# MOSFET_Driver_Sheet4.net
KiCad netlist of a schematic drawn in Altium Designer
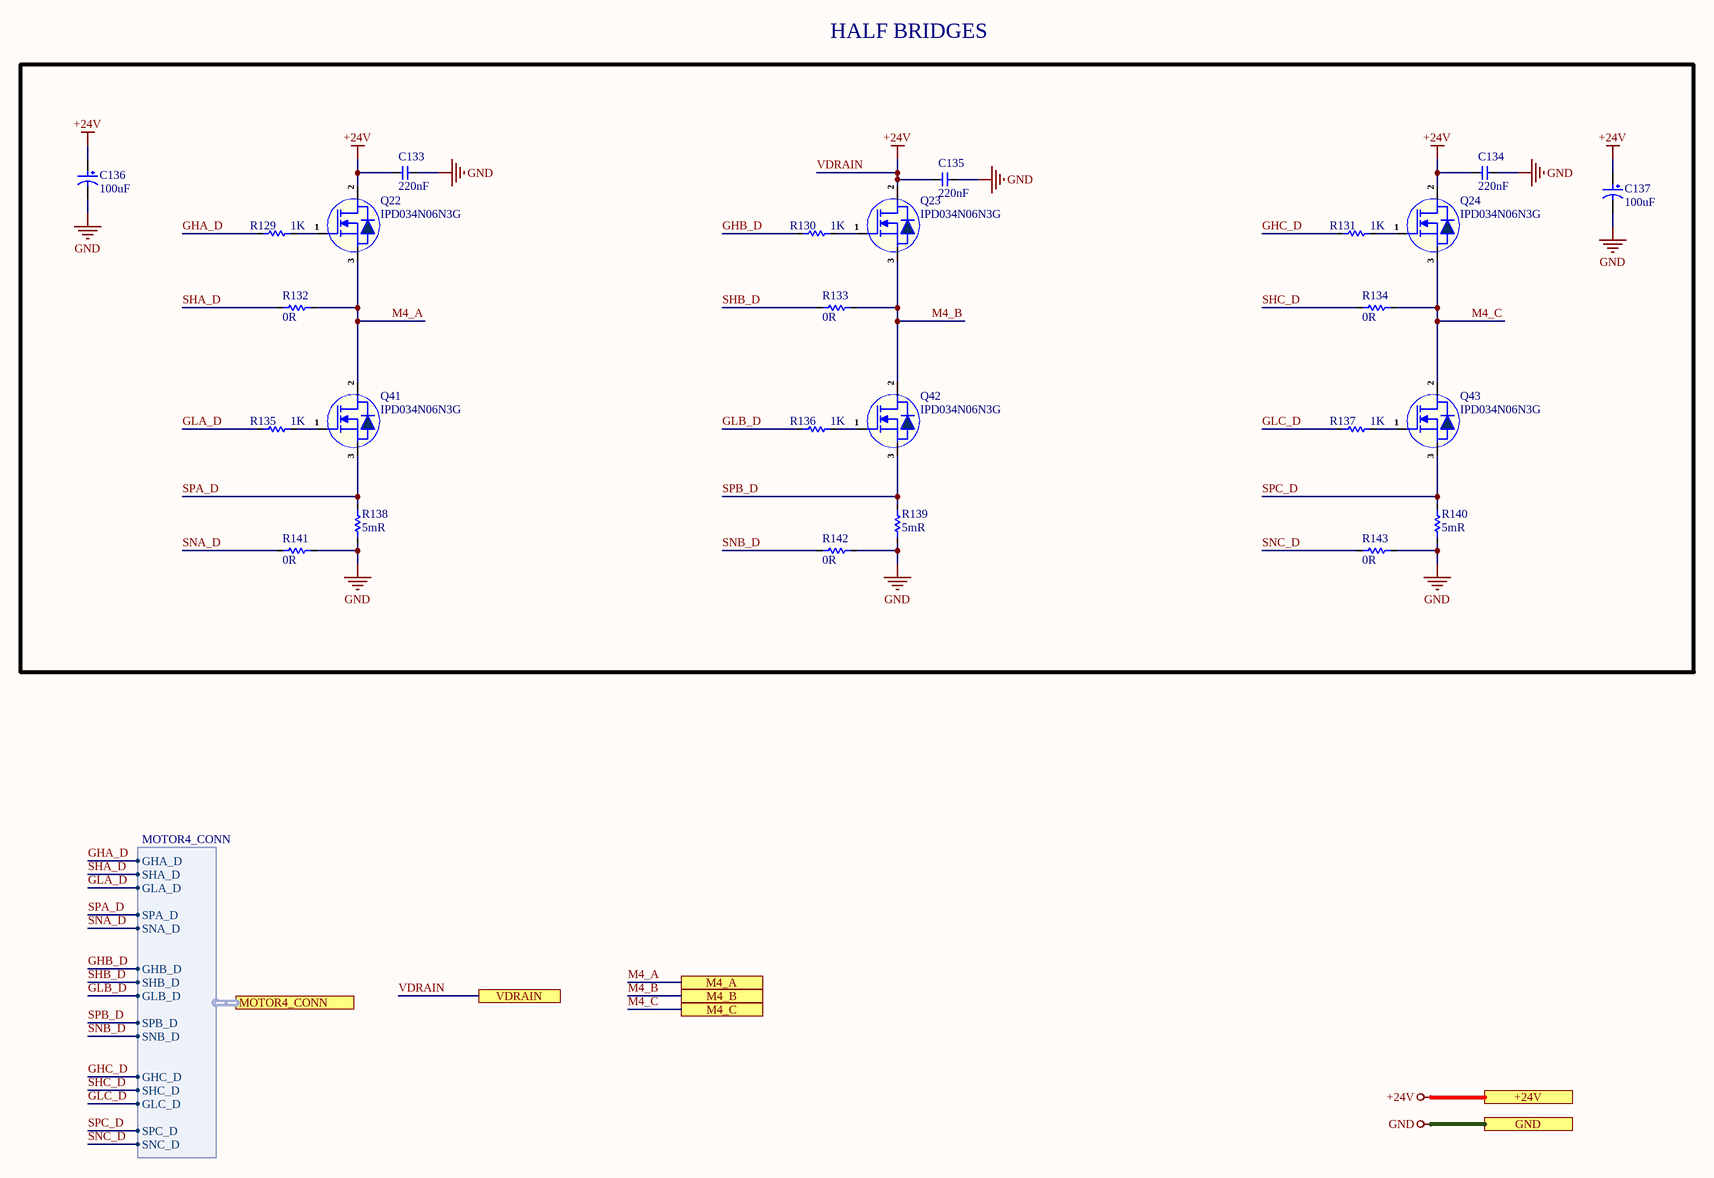
[diagram p0: MOSFET_Driver_Sheet4.SchDoc]

(export (version "E")
  (design (tool "Eeschema 10.0.6"))
  (components
    (comp (ref "C133")
      (value "220nF")
      (footprint "Cap-0805")
      (description "CAP CER 0.22UF 100V X7R 0805")
      (fields
        (field (name "MANUFACTURER") "Kyocera AVX")
        (field (name "MANUFACTURER PART NUMBER") "08051C224K4T2A")
      )
      (libsource (lib "eSpark Libraries") (part "08051C224K4T2A"))
    )
    (comp (ref "C134")
      (value "220nF")
      (footprint "Cap-0805")
      (description "CAP CER 0.22UF 100V X7R 0805")
      (fields
        (field (name "MANUFACTURER") "Kyocera AVX")
        (field (name "MANUFACTURER PART NUMBER") "08051C224K4T2A")
      )
      (libsource (lib "eSpark Libraries") (part "08051C224K4T2A"))
    )
    (comp (ref "C135")
      (value "220nF")
      (footprint "Cap-0805")
      (description "CAP CER 0.22UF 100V X7R 0805")
      (fields
        (field (name "MANUFACTURER") "Kyocera AVX")
        (field (name "MANUFACTURER PART NUMBER") "08051C224K4T2A")
      )
      (libsource (lib "eSpark Libraries") (part "08051C224K4T2A"))
    )
    (comp (ref "C136")
      (value "100uF")
      (footprint "RVT1A101M0605")
      (description "100uF 10V 55mA@120Hz ±20% SMD,D6.3xL5.4mm Aluminum Electrolytic Capacitors - SMD ROHS")
      (fields
        (field (name "MANUFACTURER") "ROQANG")
        (field (name "MANUFACTURER PART NUMBER") "RVT1A101M0605")
      )
      (libsource (lib "eSpark Libraries") (part "RVT1A101M0605"))
    )
    (comp (ref "C137")
      (value "100uF")
      (footprint "RVT1A101M0605")
      (description "100uF 10V 55mA@120Hz ±20% SMD,D6.3xL5.4mm Aluminum Electrolytic Capacitors - SMD ROHS")
      (fields
        (field (name "MANUFACTURER") "ROQANG")
        (field (name "MANUFACTURER PART NUMBER") "RVT1A101M0605")
      )
      (libsource (lib "eSpark Libraries") (part "RVT1A101M0605"))
    )
    (comp (ref "Q22")
      (value "IPD034N06N3G")
      (footprint "TO-252-2L")
      (description "MOSFET N-CH 60V 100A TO252-3")
      (fields (field (name "MANUFACTURER") "Infineon") (field (name "LCSC PART NUMBER") "C94897"))
      (libsource (lib "eSpark Libraries") (part "IPD034N06N3G"))
    )
    (comp (ref "Q23")
      (value "IPD034N06N3G")
      (footprint "TO-252-2L")
      (description "MOSFET N-CH 60V 100A TO252-3")
      (fields (field (name "MANUFACTURER") "Infineon") (field (name "LCSC PART NUMBER") "C94897"))
      (libsource (lib "eSpark Libraries") (part "IPD034N06N3G"))
    )
    (comp (ref "Q24")
      (value "IPD034N06N3G")
      (footprint "TO-252-2L")
      (description "MOSFET N-CH 60V 100A TO252-3")
      (fields (field (name "MANUFACTURER") "Infineon") (field (name "LCSC PART NUMBER") "C94897"))
      (libsource (lib "eSpark Libraries") (part "IPD034N06N3G"))
    )
    (comp (ref "Q41")
      (value "IPD034N06N3G")
      (footprint "TO-252-2L")
      (description "MOSFET N-CH 60V 100A TO252-3")
      (fields (field (name "MANUFACTURER") "Infineon") (field (name "LCSC PART NUMBER") "C94897"))
      (libsource (lib "eSpark Libraries") (part "IPD034N06N3G"))
    )
    (comp (ref "Q42")
      (value "IPD034N06N3G")
      (footprint "TO-252-2L")
      (description "MOSFET N-CH 60V 100A TO252-3")
      (fields (field (name "MANUFACTURER") "Infineon") (field (name "LCSC PART NUMBER") "C94897"))
      (libsource (lib "eSpark Libraries") (part "IPD034N06N3G"))
    )
    (comp (ref "Q43")
      (value "IPD034N06N3G")
      (footprint "TO-252-2L")
      (description "MOSFET N-CH 60V 100A TO252-3")
      (fields (field (name "MANUFACTURER") "Infineon") (field (name "LCSC PART NUMBER") "C94897"))
      (libsource (lib "eSpark Libraries") (part "IPD034N06N3G"))
    )
    (comp (ref "R129")
      (value "1K")
      (footprint "Res-0402")
      (description "RES 1K OHM 1% 1/16W 0402")
      (fields
        (field (name "MANUFACTURER") "Yageo")
        (field (name "MANUFACTURER PART NUMBER") "RC0402FR-071KL")
      )
      (libsource (lib "eSpark Libraries") (part "RC0402FR-071KL"))
    )
    (comp (ref "R130")
      (value "1K")
      (footprint "Res-0402")
      (description "RES 1K OHM 1% 1/16W 0402")
      (fields
        (field (name "MANUFACTURER") "Yageo")
        (field (name "MANUFACTURER PART NUMBER") "RC0402FR-071KL")
      )
      (libsource (lib "eSpark Libraries") (part "RC0402FR-071KL"))
    )
    (comp (ref "R131")
      (value "1K")
      (footprint "Res-0402")
      (description "RES 1K OHM 1% 1/16W 0402")
      (fields
        (field (name "MANUFACTURER") "Yageo")
        (field (name "MANUFACTURER PART NUMBER") "RC0402FR-071KL")
      )
      (libsource (lib "eSpark Libraries") (part "RC0402FR-071KL"))
    )
    (comp (ref "R132")
      (value "0R")
      (footprint "Res-0603")
      (description "RES 0 OHM JUMPER 1/10W 0603")
      (fields
        (field (name "MANUFACTURER") "Yageo")
        (field (name "MANUFACTURER PART NUMBER") "RC0603JR-070RL")
      )
      (libsource (lib "eSpark Libraries") (part "RC0603JR-070RL"))
    )
    (comp (ref "R133")
      (value "0R")
      (footprint "Res-0603")
      (description "RES 0 OHM JUMPER 1/10W 0603")
      (fields
        (field (name "MANUFACTURER") "Yageo")
        (field (name "MANUFACTURER PART NUMBER") "RC0603JR-070RL")
      )
      (libsource (lib "eSpark Libraries") (part "RC0603JR-070RL"))
    )
    (comp (ref "R134")
      (value "0R")
      (footprint "Res-0603")
      (description "RES 0 OHM JUMPER 1/10W 0603")
      (fields
        (field (name "MANUFACTURER") "Yageo")
        (field (name "MANUFACTURER PART NUMBER") "RC0603JR-070RL")
      )
      (libsource (lib "eSpark Libraries") (part "RC0603JR-070RL"))
    )
    (comp (ref "R135")
      (value "1K")
      (footprint "Res-0402")
      (description "RES 1K OHM 1% 1/16W 0402")
      (fields
        (field (name "MANUFACTURER") "Yageo")
        (field (name "MANUFACTURER PART NUMBER") "RC0402FR-071KL")
      )
      (libsource (lib "eSpark Libraries") (part "RC0402FR-071KL"))
    )
    (comp (ref "R136")
      (value "1K")
      (footprint "Res-0402")
      (description "RES 1K OHM 1% 1/16W 0402")
      (fields
        (field (name "MANUFACTURER") "Yageo")
        (field (name "MANUFACTURER PART NUMBER") "RC0402FR-071KL")
      )
      (libsource (lib "eSpark Libraries") (part "RC0402FR-071KL"))
    )
    (comp (ref "R137")
      (value "1K")
      (footprint "Res-0402")
      (description "RES 1K OHM 1% 1/16W 0402")
      (fields
        (field (name "MANUFACTURER") "Yageo")
        (field (name "MANUFACTURER PART NUMBER") "RC0402FR-071KL")
      )
      (libsource (lib "eSpark Libraries") (part "RC0402FR-071KL"))
    )
    (comp (ref "R138")
      (value "5mR")
      (footprint "Res-1206")
      (description "1W 5mΩ ±1% 1206 Current Sense Resistors/Shunt Resistors ROHS")
      (fields
        (field (name "MANUFACTURER") "FORT")
        (field (name "MANUFACTURER PART NUMBER") "CUM1206-15FR005")
      )
      (libsource (lib "eSpark Libraries") (part "CUM1206-15FR005"))
    )
    (comp (ref "R139")
      (value "5mR")
      (footprint "Res-1206")
      (description "1W 5mΩ ±1% 1206 Current Sense Resistors/Shunt Resistors ROHS")
      (fields
        (field (name "MANUFACTURER") "FORT")
        (field (name "MANUFACTURER PART NUMBER") "CUM1206-15FR005")
      )
      (libsource (lib "eSpark Libraries") (part "CUM1206-15FR005"))
    )
    (comp (ref "R140")
      (value "5mR")
      (footprint "Res-1206")
      (description "1W 5mΩ ±1% 1206 Current Sense Resistors/Shunt Resistors ROHS")
      (fields
        (field (name "MANUFACTURER") "FORT")
        (field (name "MANUFACTURER PART NUMBER") "CUM1206-15FR005")
      )
      (libsource (lib "eSpark Libraries") (part "CUM1206-15FR005"))
    )
    (comp (ref "R141")
      (value "0R")
      (footprint "Res-0603")
      (description "RES 0 OHM JUMPER 1/10W 0603")
      (fields
        (field (name "MANUFACTURER") "Yageo")
        (field (name "MANUFACTURER PART NUMBER") "RC0603JR-070RL")
      )
      (libsource (lib "eSpark Libraries") (part "RC0603JR-070RL"))
    )
    (comp (ref "R142")
      (value "0R")
      (footprint "Res-0603")
      (description "RES 0 OHM JUMPER 1/10W 0603")
      (fields
        (field (name "MANUFACTURER") "Yageo")
        (field (name "MANUFACTURER PART NUMBER") "RC0603JR-070RL")
      )
      (libsource (lib "eSpark Libraries") (part "RC0603JR-070RL"))
    )
    (comp (ref "R143")
      (value "0R")
      (footprint "Res-0603")
      (description "RES 0 OHM JUMPER 1/10W 0603")
      (fields
        (field (name "MANUFACTURER") "Yageo")
        (field (name "MANUFACTURER PART NUMBER") "RC0603JR-070RL")
      )
      (libsource (lib "eSpark Libraries") (part "RC0603JR-070RL"))
    )
  )
  (nets
    (net (code "2") (name "+24V") (class "Default")
      (node (ref "C133") (pin "2") (pinfunction "2_2") (pintype "passive"))
      (node (ref "C134") (pin "2") (pinfunction "2_2") (pintype "passive"))
      (node (ref "C135") (pin "2") (pinfunction "2_2") (pintype "passive"))
      (node (ref "C136") (pin "1") (pintype "passive"))
      (node (ref "C137") (pin "1") (pintype "passive"))
      (node (ref "Q22") (pin "2") (pinfunction "D_2") (pintype "passive"))
      (node (ref "Q23") (pin "2") (pinfunction "D_2") (pintype "passive"))
      (node (ref "Q24") (pin "2") (pinfunction "D_2") (pintype "passive"))
    )
    (net (code "3") (name "/GHA_D") (class "Default")
      (node (ref "R129") (pin "1") (pinfunction "1_1") (pintype "passive"))
    )
    (net (code "4") (name "/GHB_D") (class "Default")
      (node (ref "R130") (pin "1") (pinfunction "1_1") (pintype "passive"))
    )
    (net (code "5") (name "/GHC_D") (class "Default")
      (node (ref "R131") (pin "1") (pinfunction "1_1") (pintype "passive"))
    )
    (net (code "6") (name "/GLA_D") (class "Default")
      (node (ref "R135") (pin "1") (pinfunction "1_1") (pintype "passive"))
    )
    (net (code "7") (name "/GLB_D") (class "Default")
      (node (ref "R136") (pin "1") (pinfunction "1_1") (pintype "passive"))
    )
    (net (code "8") (name "/GLC_D") (class "Default")
      (node (ref "R137") (pin "1") (pinfunction "1_1") (pintype "passive"))
    )
    (net (code "9") (name "/M4_A") (class "Default")
      (node (ref "Q22") (pin "3") (pinfunction "S_3") (pintype "passive"))
      (node (ref "Q41") (pin "2") (pinfunction "D_2") (pintype "passive"))
      (node (ref "R132") (pin "1") (pinfunction "1_1") (pintype "passive"))
    )
    (net (code "10") (name "/M4_B") (class "Default")
      (node (ref "Q23") (pin "3") (pinfunction "S_3") (pintype "passive"))
      (node (ref "Q42") (pin "2") (pinfunction "D_2") (pintype "passive"))
      (node (ref "R133") (pin "1") (pinfunction "1_1") (pintype "passive"))
    )
    (net (code "11") (name "/M4_C") (class "Default")
      (node (ref "Q24") (pin "3") (pinfunction "S_3") (pintype "passive"))
      (node (ref "Q43") (pin "2") (pinfunction "D_2") (pintype "passive"))
      (node (ref "R134") (pin "1") (pinfunction "1_1") (pintype "passive"))
    )
    (net (code "12") (name "/SHA_D") (class "Default")
      (node (ref "R132") (pin "2") (pinfunction "2_2") (pintype "passive"))
    )
    (net (code "13") (name "/SHB_D") (class "Default")
      (node (ref "R133") (pin "2") (pinfunction "2_2") (pintype "passive"))
    )
    (net (code "14") (name "/SHC_D") (class "Default")
      (node (ref "R134") (pin "2") (pinfunction "2_2") (pintype "passive"))
    )
    (net (code "15") (name "/SNA_D") (class "Default")
      (node (ref "R141") (pin "2") (pinfunction "2_2") (pintype "passive"))
    )
    (net (code "16") (name "/SNB_D") (class "Default")
      (node (ref "R142") (pin "2") (pinfunction "2_2") (pintype "passive"))
    )
    (net (code "17") (name "/SNC_D") (class "Default")
      (node (ref "R143") (pin "2") (pinfunction "2_2") (pintype "passive"))
    )
    (net (code "18") (name "/SPA_D") (class "Default")
      (node (ref "Q41") (pin "3") (pinfunction "S_3") (pintype "passive"))
      (node (ref "R138") (pin "2") (pinfunction "2_2") (pintype "passive"))
    )
    (net (code "19") (name "/SPB_D") (class "Default")
      (node (ref "Q42") (pin "3") (pinfunction "S_3") (pintype "passive"))
      (node (ref "R139") (pin "2") (pinfunction "2_2") (pintype "passive"))
    )
    (net (code "20") (name "/SPC_D") (class "Default")
      (node (ref "Q43") (pin "3") (pinfunction "S_3") (pintype "passive"))
      (node (ref "R140") (pin "2") (pinfunction "2_2") (pintype "passive"))
    )
    (net (code "22") (name "GND") (class "Default")
      (node (ref "C133") (pin "1") (pinfunction "1_1") (pintype "passive"))
      (node (ref "C134") (pin "1") (pinfunction "1_1") (pintype "passive"))
      (node (ref "C135") (pin "1") (pinfunction "1_1") (pintype "passive"))
      (node (ref "C136") (pin "2") (pintype "passive"))
      (node (ref "C137") (pin "2") (pintype "passive"))
      (node (ref "R138") (pin "1") (pinfunction "1_1") (pintype "passive"))
      (node (ref "R139") (pin "1") (pinfunction "1_1") (pintype "passive"))
      (node (ref "R140") (pin "1") (pinfunction "1_1") (pintype "passive"))
      (node (ref "R141") (pin "1") (pinfunction "1_1") (pintype "passive"))
      (node (ref "R142") (pin "1") (pinfunction "1_1") (pintype "passive"))
      (node (ref "R143") (pin "1") (pinfunction "1_1") (pintype "passive"))
    )
    (net (code "23") (name "Net-(Q22-G)") (class "Default")
      (node (ref "Q22") (pin "1") (pinfunction "G_1") (pintype "passive"))
      (node (ref "R129") (pin "2") (pinfunction "2_2") (pintype "passive"))
    )
    (net (code "24") (name "Net-(Q23-G)") (class "Default")
      (node (ref "Q23") (pin "1") (pinfunction "G_1") (pintype "passive"))
      (node (ref "R130") (pin "2") (pinfunction "2_2") (pintype "passive"))
    )
    (net (code "25") (name "Net-(Q24-G)") (class "Default")
      (node (ref "Q24") (pin "1") (pinfunction "G_1") (pintype "passive"))
      (node (ref "R131") (pin "2") (pinfunction "2_2") (pintype "passive"))
    )
    (net (code "26") (name "Net-(Q41-G)") (class "Default")
      (node (ref "Q41") (pin "1") (pinfunction "G_1") (pintype "passive"))
      (node (ref "R135") (pin "2") (pinfunction "2_2") (pintype "passive"))
    )
    (net (code "27") (name "Net-(Q42-G)") (class "Default")
      (node (ref "Q42") (pin "1") (pinfunction "G_1") (pintype "passive"))
      (node (ref "R136") (pin "2") (pinfunction "2_2") (pintype "passive"))
    )
    (net (code "28") (name "Net-(Q43-G)") (class "Default")
      (node (ref "Q43") (pin "1") (pinfunction "G_1") (pintype "passive"))
      (node (ref "R137") (pin "2") (pinfunction "2_2") (pintype "passive"))
    )
  )
)
